# pol.net
KiCad netlist of a schematic drawn in EAGLE
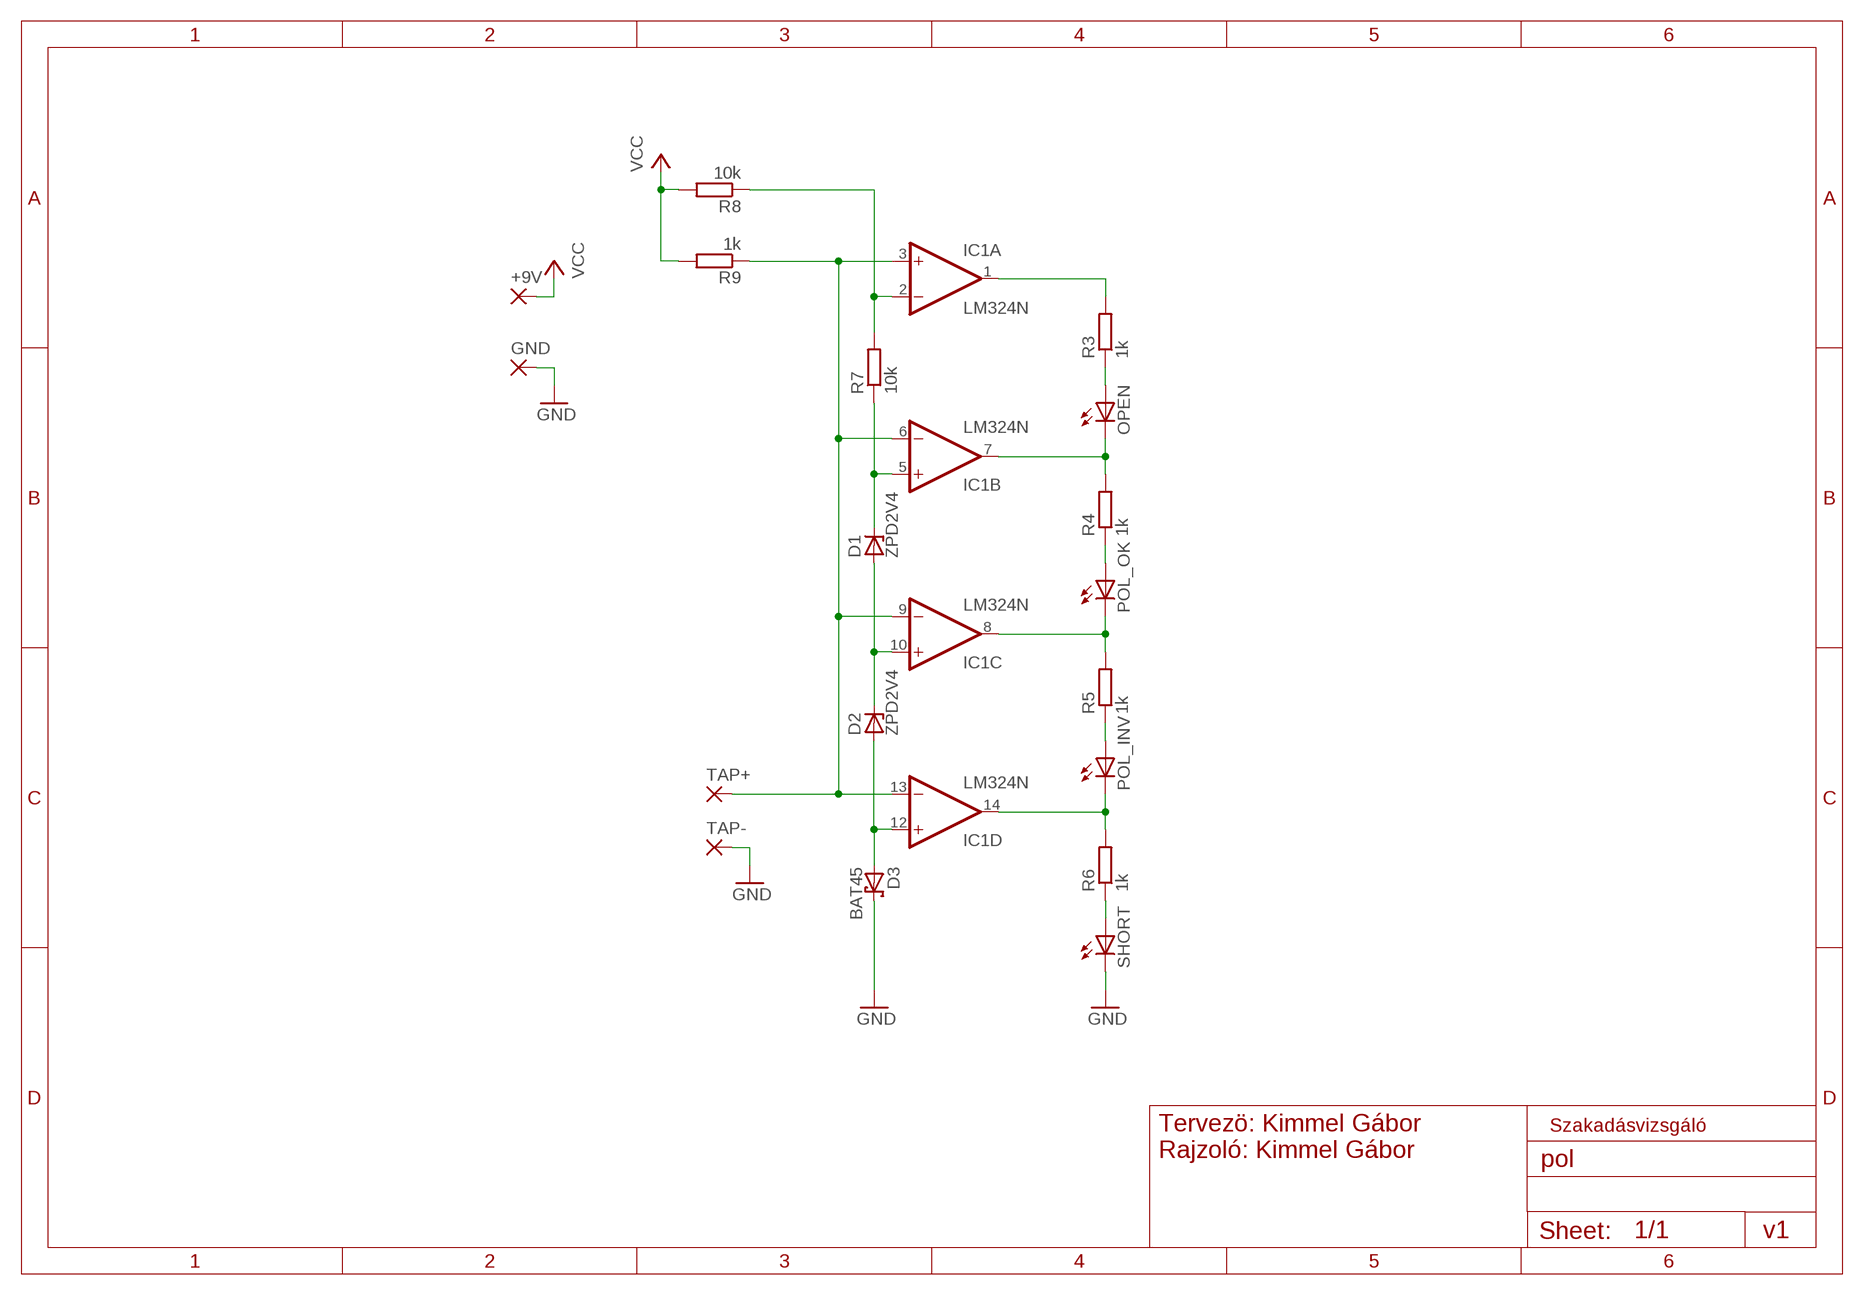
[diagram p0: schematic, sheet 1]

(export (version "E")
  (design (tool "Eeschema 10.0.6"))
  (components
    (comp (ref "+9V")
      (value "2,54/1,0")
      (footprint "eagle-import:2,54_1,0")
      (libsource (lib "eagle-import") (part "2,54/1,0"))
    )
    (comp (ref "D1")
      (value "ZPD2V4")
      (footprint "eagle-import:DO35Z10")
      (libsource (lib "eagle-import") (part "ZPD"))
    )
    (comp (ref "D2")
      (value "ZPD2V4")
      (footprint "eagle-import:DO35Z10")
      (libsource (lib "eagle-import") (part "ZPD"))
    )
    (comp (ref "D3")
      (value "BAT45")
      (footprint "eagle-import:DO35-10")
      (libsource (lib "eagle-import") (part "BAT42"))
    )
    (comp (ref "GND")
      (value "2,54/1,0")
      (footprint "eagle-import:2,54_1,0")
      (libsource (lib "eagle-import") (part "2,54/1,0"))
    )
    (comp (ref "IC1")
      (value "LM324N")
      (footprint "eagle-import:DIL14")
      (libsource (lib "eagle-import") (part "LM324N"))
    )
    (comp (ref "OPEN")
      (value "LED5MM")
      (footprint "eagle-import:LED5MM")
      (libsource (lib "eagle-import") (part "LED5MM"))
    )
    (comp (ref "POL_INV")
      (value "LED5MM")
      (footprint "eagle-import:LED5MM")
      (libsource (lib "eagle-import") (part "LED5MM"))
    )
    (comp (ref "POL_OK")
      (value "LED5MM")
      (footprint "eagle-import:LED5MM")
      (libsource (lib "eagle-import") (part "LED5MM"))
    )
    (comp (ref "R3")
      (value "1k")
      (footprint "eagle-import:0309_12")
      (libsource (lib "eagle-import") (part "R-EU_0309/12"))
    )
    (comp (ref "R4")
      (value "1k")
      (footprint "eagle-import:0309_12")
      (libsource (lib "eagle-import") (part "R-EU_0309/12"))
    )
    (comp (ref "R5")
      (value "1k")
      (footprint "eagle-import:0309_12")
      (libsource (lib "eagle-import") (part "R-EU_0309/12"))
    )
    (comp (ref "R6")
      (value "1k")
      (footprint "eagle-import:0309_12")
      (libsource (lib "eagle-import") (part "R-EU_0309/12"))
    )
    (comp (ref "R7")
      (value "10k")
      (footprint "eagle-import:0309_12")
      (libsource (lib "eagle-import") (part "R-EU_0309/12"))
    )
    (comp (ref "R8")
      (value "10k")
      (footprint "eagle-import:0309_12")
      (libsource (lib "eagle-import") (part "R-EU_0309/12"))
    )
    (comp (ref "R9")
      (value "1k")
      (footprint "eagle-import:0309_12")
      (libsource (lib "eagle-import") (part "R-EU_0309/12"))
    )
    (comp (ref "SHORT")
      (value "LED5MM")
      (footprint "eagle-import:LED5MM")
      (libsource (lib "eagle-import") (part "LED5MM"))
    )
    (comp (ref "TAP+")
      (value "2,54/1,0")
      (footprint "eagle-import:2,54_1,0")
      (libsource (lib "eagle-import") (part "2,54/1,0"))
    )
    (comp (ref "TAP-")
      (value "2,54/1,0")
      (footprint "eagle-import:2,54_1,0")
      (libsource (lib "eagle-import") (part "2,54/1,0"))
    )
  )
  (nets
    (net (code "1") (name "GND") (class "Default")
      (node (ref "D3") (pin "C") (pinfunction "C_C") (pintype "passive"))
      (node (ref "GND") (pin "1") (pinfunction "P_1") (pintype "passive"))
      (node (ref "SHORT") (pin "K") (pinfunction "C_K") (pintype "passive"))
      (node (ref "TAP-") (pin "1") (pinfunction "P_1") (pintype "passive"))
    )
    (net (code "2") (name "Net-(IC1A-+IN)") (class "Default")
      (node (ref "IC1") (pin "13") (pinfunction "-IN_13") (pintype "input"))
      (node (ref "IC1") (pin "3") (pinfunction "+IN_3") (pintype "input"))
      (node (ref "IC1") (pin "6") (pinfunction "-IN_6") (pintype "input"))
      (node (ref "IC1") (pin "9") (pinfunction "-IN_9") (pintype "input"))
      (node (ref "R9") (pin "1") (pinfunction "1_1") (pintype "passive"))
      (node (ref "TAP+") (pin "1") (pinfunction "P_1") (pintype "passive"))
    )
    (net (code "3") (name "Net-(IC1A--IN)") (class "Default")
      (node (ref "IC1") (pin "2") (pinfunction "-IN_2") (pintype "input"))
      (node (ref "R7") (pin "2") (pinfunction "2_2") (pintype "passive"))
      (node (ref "R8") (pin "1") (pinfunction "1_1") (pintype "passive"))
    )
    (net (code "4") (name "Net-(IC1A-OUT)") (class "Default")
      (node (ref "IC1") (pin "1") (pinfunction "OUT_1") (pintype "output"))
      (node (ref "R3") (pin "2") (pinfunction "2_2") (pintype "passive"))
    )
    (net (code "5") (name "Net-(IC1B-+IN)") (class "Default")
      (node (ref "D1") (pin "C") (pinfunction "C_C") (pintype "passive"))
      (node (ref "IC1") (pin "5") (pinfunction "+IN_5") (pintype "input"))
      (node (ref "R7") (pin "1") (pinfunction "1_1") (pintype "passive"))
    )
    (net (code "6") (name "Net-(IC1B-OUT)") (class "Default")
      (node (ref "IC1") (pin "7") (pinfunction "OUT_7") (pintype "output"))
      (node (ref "OPEN") (pin "K") (pinfunction "C_K") (pintype "passive"))
      (node (ref "R4") (pin "2") (pinfunction "2_2") (pintype "passive"))
    )
    (net (code "7") (name "Net-(IC1C-+IN)") (class "Default")
      (node (ref "D1") (pin "A") (pinfunction "A_A") (pintype "passive"))
      (node (ref "D2") (pin "C") (pinfunction "C_C") (pintype "passive"))
      (node (ref "IC1") (pin "10") (pinfunction "+IN_10") (pintype "input"))
    )
    (net (code "8") (name "Net-(IC1C-OUT)") (class "Default")
      (node (ref "IC1") (pin "8") (pinfunction "OUT_8") (pintype "output"))
      (node (ref "POL_OK") (pin "K") (pinfunction "C_K") (pintype "passive"))
      (node (ref "R5") (pin "2") (pinfunction "2_2") (pintype "passive"))
    )
    (net (code "9") (name "Net-(IC1D-+IN)") (class "Default")
      (node (ref "D2") (pin "A") (pinfunction "A_A") (pintype "passive"))
      (node (ref "D3") (pin "A") (pinfunction "A_A") (pintype "passive"))
      (node (ref "IC1") (pin "12") (pinfunction "+IN_12") (pintype "input"))
    )
    (net (code "10") (name "Net-(IC1D-OUT)") (class "Default")
      (node (ref "IC1") (pin "14") (pinfunction "OUT_14") (pintype "output"))
      (node (ref "POL_INV") (pin "K") (pinfunction "C_K") (pintype "passive"))
      (node (ref "R6") (pin "2") (pinfunction "2_2") (pintype "passive"))
    )
    (net (code "11") (name "Net-(OPEN-PadA)") (class "Default")
      (node (ref "OPEN") (pin "A") (pinfunction "A_A") (pintype "passive"))
      (node (ref "R3") (pin "1") (pinfunction "1_1") (pintype "passive"))
    )
    (net (code "12") (name "Net-(POL_INV-PadA)") (class "Default")
      (node (ref "POL_INV") (pin "A") (pinfunction "A_A") (pintype "passive"))
      (node (ref "R5") (pin "1") (pinfunction "1_1") (pintype "passive"))
    )
    (net (code "13") (name "Net-(POL_OK-PadA)") (class "Default")
      (node (ref "POL_OK") (pin "A") (pinfunction "A_A") (pintype "passive"))
      (node (ref "R4") (pin "1") (pinfunction "1_1") (pintype "passive"))
    )
    (net (code "14") (name "Net-(R6-Pad1)") (class "Default")
      (node (ref "R6") (pin "1") (pinfunction "1_1") (pintype "passive"))
      (node (ref "SHORT") (pin "A") (pinfunction "A_A") (pintype "passive"))
    )
    (net (code "15") (name "VCC") (class "Default")
      (node (ref "+9V") (pin "1") (pinfunction "P_1") (pintype "passive"))
      (node (ref "R8") (pin "2") (pinfunction "2_2") (pintype "passive"))
      (node (ref "R9") (pin "2") (pinfunction "2_2") (pintype "passive"))
    )
  )
)
